# pictest_dram_2021-04-17.net
KiCad netlist of a schematic drawn in EasyEDA
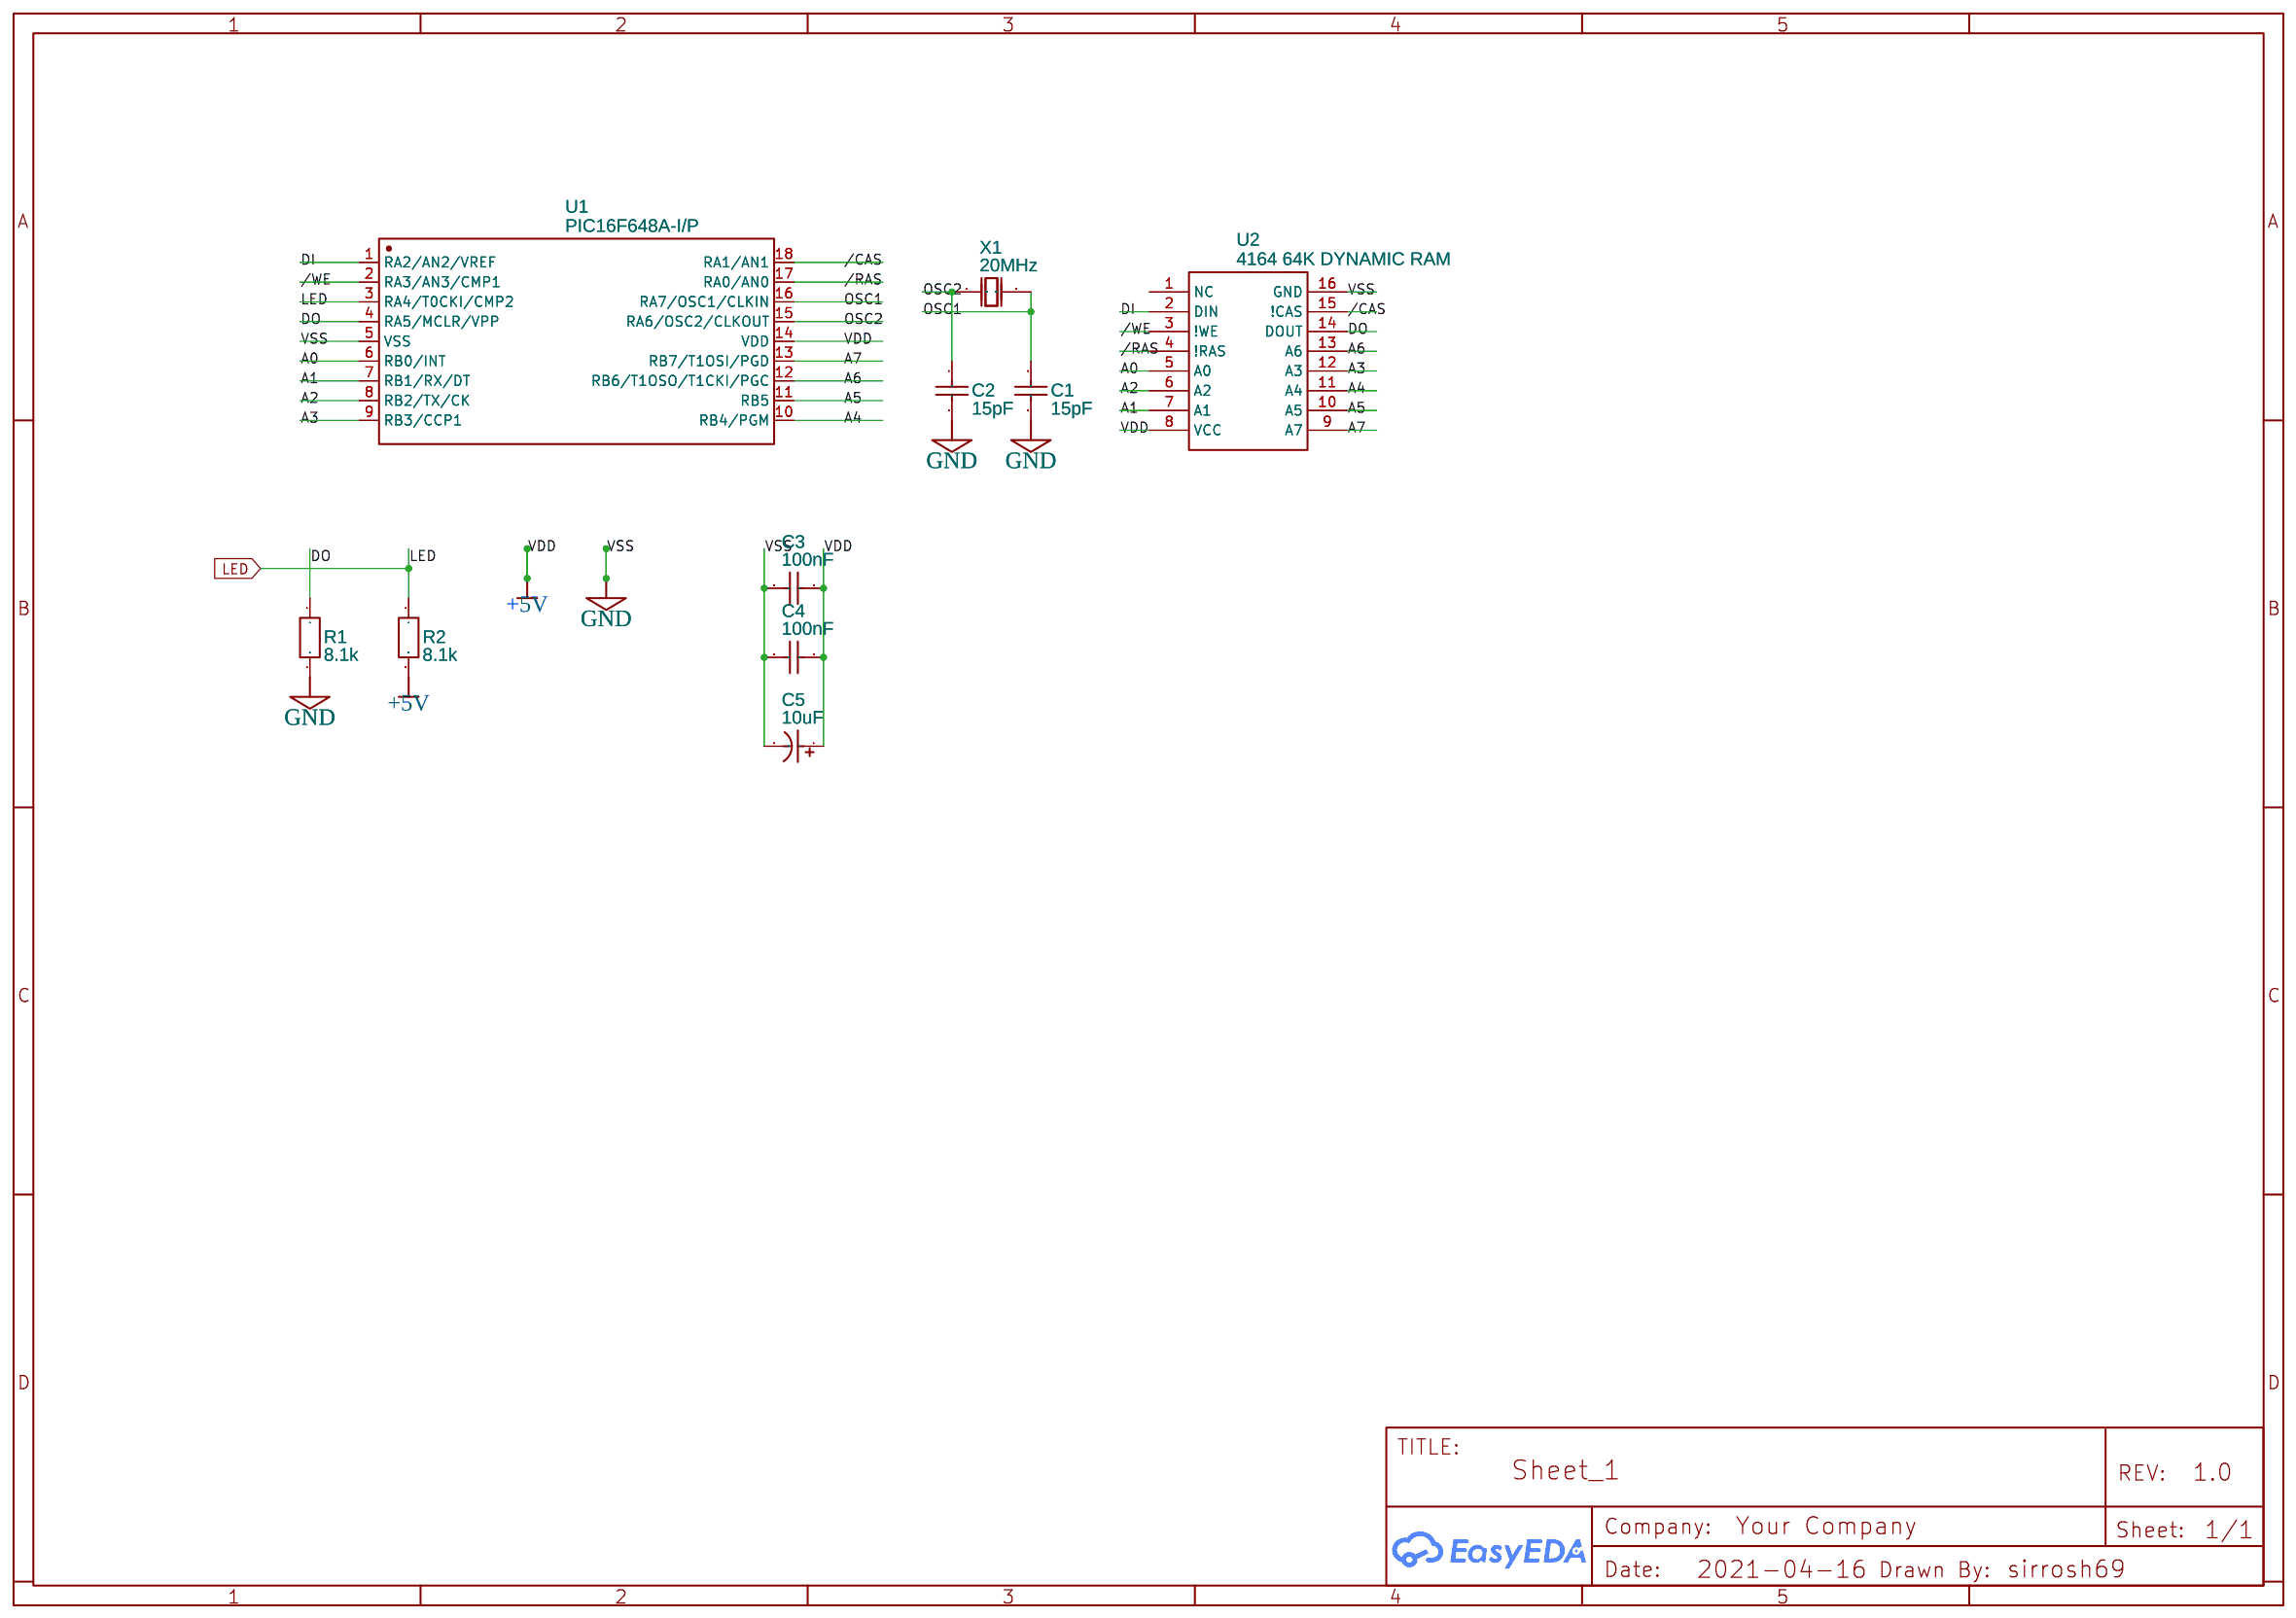
[diagram p0: schematic sheet]

(export (version "E")
  (design (tool "Eeschema 10.0.6"))
  (components
    (comp (ref "C1")
      (value "15pF")
      (fields
        (field (name "BOM_Manufacturer Part") "Monolithic 15pF (150) ±5%")
        (field (name "BOM_Supplier Part") "C32131")
      )
      (libsource (lib "") (part "Monolithic 15pF (150) ±5%"))
    )
    (comp (ref "C2")
      (value "15pF")
      (fields
        (field (name "BOM_Manufacturer Part") "Monolithic 15pF (150) ±5%")
        (field (name "BOM_Supplier Part") "C32131")
      )
      (libsource (lib "") (part "Monolithic 15pF (150) ±5%"))
    )
    (comp (ref "C3")
      (value "100nF")
      (fields
        (field (name "BOM_Manufacturer Part") "0.1UF(104) +-20% 63v")
        (field (name "BOM_Supplier Part") "C19355")
      )
      (libsource (lib "") (part "100nF"))
    )
    (comp (ref "C4")
      (value "100nF")
      (fields
        (field (name "BOM_Manufacturer Part") "0.1UF(104) +-20% 63v")
        (field (name "BOM_Supplier Part") "C19355")
      )
      (libsource (lib "") (part "100nF"))
    )
    (comp (ref "C5")
      (value "10uF")
      (fields
        (field (name "BOM_Manufacturer Part") "10uF 16V 5*11")
        (field (name "BOM_Supplier Part") "C43799")
      )
      (libsource (lib "") (part "10uF 16V 5*11"))
    )
    (comp (ref "R1") (value "8.1k") (libsource (lib "") (part "R_0603_EU")))
    (comp (ref "R2") (value "8.1k") (libsource (lib "") (part "R_0603_EU")))
    (comp (ref "U1")
      (value "PIC16F648A-I/P")
      (fields (field (name "BOM_Supplier Part") "C50894"))
      (libsource (lib "") (part "PIC16F648A-I/P"))
    )
    (comp (ref "U2")
      (value "4164 64K DYNAMIC RAM")
      (fields (field (name "BOM_Supplier Part") "HM4864-3"))
      (libsource (lib "") (part "4164 64K DYNAMIC RAM"))
    )
    (comp (ref "X1")
      (value "20MHz")
      (fields
        (field (name "BOM_Manufacturer Part") "49S DIP Crystal insulation film")
        (field (name "BOM_Supplier Part") "C35018")
      )
      (libsource (lib "") (part "49S DIP Crystal insulation film"))
    )
  )
  (nets
    (net (code "1") (name "+5V") (class "Default")
      (node (ref "C3") (pin "2") (pinfunction "2_2") (pintype "input"))
      (node (ref "C4") (pin "2") (pinfunction "2_2") (pintype "input"))
      (node (ref "C5") (pin "1") (pinfunction "1_1") (pintype "input"))
      (node (ref "R2") (pin "2") (pinfunction "2_2") (pintype "unspecified"))
      (node (ref "U1") (pin "14") (pinfunction "VDD_14") (pintype "unspecified"))
      (node (ref "U2") (pin "8") (pinfunction "VCC_8") (pintype "unspecified"))
    )
    (net (code "2") (name "/A0") (class "Default")
      (node (ref "U1") (pin "6") (pinfunction "RB0/INT_6") (pintype "unspecified"))
      (node (ref "U2") (pin "5") (pinfunction "A0_5") (pintype "unspecified"))
    )
    (net (code "3") (name "/A1") (class "Default")
      (node (ref "U1") (pin "7") (pinfunction "RB1/RX/DT_7") (pintype "unspecified"))
      (node (ref "U2") (pin "7") (pinfunction "A1_7") (pintype "unspecified"))
    )
    (net (code "4") (name "/A2") (class "Default")
      (node (ref "U1") (pin "8") (pinfunction "RB2/TX/CK_8") (pintype "unspecified"))
      (node (ref "U2") (pin "6") (pinfunction "A2_6") (pintype "unspecified"))
    )
    (net (code "5") (name "/A3") (class "Default")
      (node (ref "U1") (pin "9") (pinfunction "RB3/CCP1_9") (pintype "unspecified"))
      (node (ref "U2") (pin "12") (pinfunction "A3_12") (pintype "unspecified"))
    )
    (net (code "6") (name "/A4") (class "Default")
      (node (ref "U1") (pin "10") (pinfunction "RB4/PGM_10") (pintype "unspecified"))
      (node (ref "U2") (pin "11") (pinfunction "A4_11") (pintype "unspecified"))
    )
    (net (code "7") (name "/A5") (class "Default")
      (node (ref "U1") (pin "11") (pinfunction "RB5_11") (pintype "unspecified"))
      (node (ref "U2") (pin "10") (pinfunction "A5_10") (pintype "unspecified"))
    )
    (net (code "8") (name "/A6") (class "Default")
      (node (ref "U1") (pin "12") (pinfunction "RB6/T1OSO/T1CKI/PGC_12") (pintype "unspecified"))
      (node (ref "U2") (pin "13") (pinfunction "A6_13") (pintype "unspecified"))
    )
    (net (code "9") (name "/A7") (class "Default")
      (node (ref "U1") (pin "13") (pinfunction "RB7/T1OSI/PGD_13") (pintype "unspecified"))
      (node (ref "U2") (pin "9") (pinfunction "A7_9") (pintype "unspecified"))
    )
    (net (code "10") (name "/DI") (class "Default")
      (node (ref "U1") (pin "1") (pinfunction "RA2/AN2/VREF_1") (pintype "unspecified"))
      (node (ref "U2") (pin "2") (pinfunction "DIN_2") (pintype "unspecified"))
    )
    (net (code "11") (name "/DO") (class "Default")
      (node (ref "R1") (pin "1") (pinfunction "1_1") (pintype "unspecified"))
      (node (ref "U1") (pin "4") (pinfunction "RA5/MCLR/VPP_4") (pintype "unspecified"))
      (node (ref "U2") (pin "14") (pinfunction "DOUT_14") (pintype "unspecified"))
    )
    (net (code "12") (name "/OSC1") (class "Default")
      (node (ref "C1") (pin "2") (pinfunction "2_2") (pintype "input"))
      (node (ref "U1") (pin "16") (pinfunction "RA7/OSC1/CLKIN_16") (pintype "unspecified"))
      (node (ref "X1") (pin "2") (pinfunction "OSC2_2") (pintype "input"))
    )
    (net (code "13") (name "/OSC2") (class "Default")
      (node (ref "C2") (pin "2") (pinfunction "2_2") (pintype "input"))
      (node (ref "U1") (pin "15") (pinfunction "RA6/OSC2/CLKOUT_15") (pintype "unspecified"))
      (node (ref "X1") (pin "1") (pinfunction "OSC1_1") (pintype "input"))
    )
    (net (code "14") (name "/{slash}CAS") (class "Default")
      (node (ref "U1") (pin "18") (pinfunction "RA1/AN1_18") (pintype "unspecified"))
      (node (ref "U2") (pin "15") (pinfunction "!CAS_15") (pintype "unspecified"))
    )
    (net (code "15") (name "/{slash}RAS") (class "Default")
      (node (ref "U1") (pin "17") (pinfunction "RA0/AN0_17") (pintype "unspecified"))
      (node (ref "U2") (pin "4") (pinfunction "!RAS_4") (pintype "unspecified"))
    )
    (net (code "16") (name "/{slash}WE") (class "Default")
      (node (ref "U1") (pin "2") (pinfunction "RA3/AN3/CMP1_2") (pintype "unspecified"))
      (node (ref "U2") (pin "3") (pinfunction "!WE_3") (pintype "unspecified"))
    )
    (net (code "17") (name "GND") (class "Default")
      (node (ref "C1") (pin "1") (pinfunction "1_1") (pintype "input"))
      (node (ref "C2") (pin "1") (pinfunction "1_1") (pintype "input"))
      (node (ref "C3") (pin "1") (pinfunction "1_1") (pintype "input"))
      (node (ref "C4") (pin "1") (pinfunction "1_1") (pintype "input"))
      (node (ref "C5") (pin "2") (pinfunction "2_2") (pintype "input"))
      (node (ref "R1") (pin "2") (pinfunction "2_2") (pintype "unspecified"))
      (node (ref "U1") (pin "5") (pinfunction "VSS_5") (pintype "unspecified"))
      (node (ref "U2") (pin "16") (pinfunction "GND_16") (pintype "unspecified"))
    )
    (net (code "18") (name "LED") (class "Default")
      (node (ref "R2") (pin "1") (pinfunction "1_1") (pintype "unspecified"))
      (node (ref "U1") (pin "3") (pinfunction "RA4/T0CKI/CMP2_3") (pintype "unspecified"))
    )
    (net (code "19") (name "unconnected-(U2-NC-Pad1)") (class "Default")
      (node (ref "U2") (pin "1") (pinfunction "NC_1") (pintype "unspecified"))
    )
  )
)
